# untitled.net
KiCad netlist of a schematic drawn in EAGLE
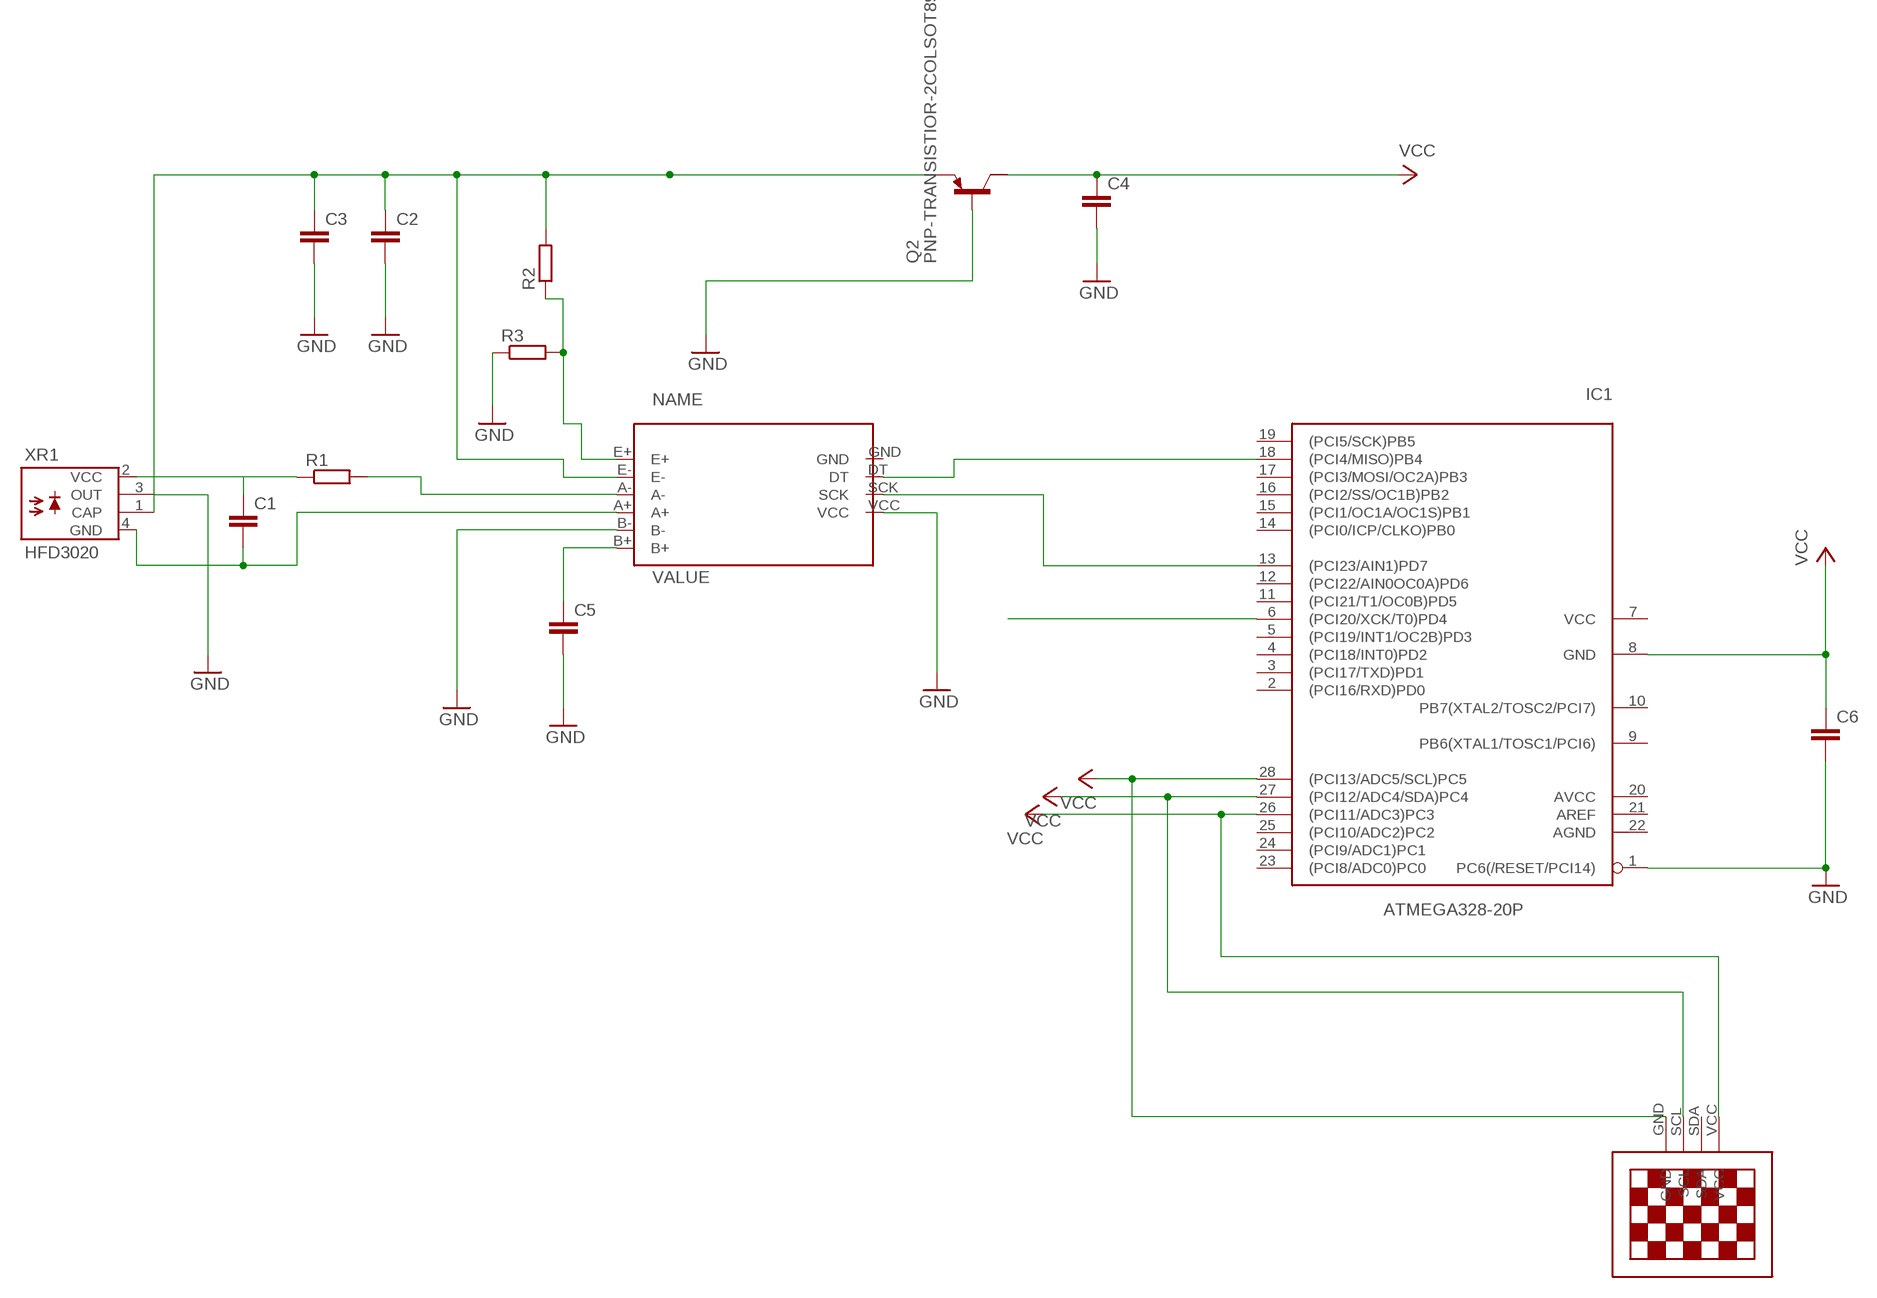
[diagram p0: schematic, sheet 1]

(export (version "E")
  (design (tool "Eeschema 10.0.6"))
  (components
    (comp (ref "C1")
      (value "C2,5-3")
      (footprint "eagle-import:C2.5-3")
      (libsource (lib "eagle-import") (part "C2,5-3"))
    )
    (comp (ref "C2")
      (value "C2,5-3")
      (footprint "eagle-import:C2.5-3")
      (libsource (lib "eagle-import") (part "C2,5-3"))
    )
    (comp (ref "C3")
      (value "C2,5-3")
      (footprint "eagle-import:C2.5-3")
      (libsource (lib "eagle-import") (part "C2,5-3"))
    )
    (comp (ref "C4")
      (value "C2,5-3")
      (footprint "eagle-import:C2.5-3")
      (libsource (lib "eagle-import") (part "C2,5-3"))
    )
    (comp (ref "C5")
      (value "C2,5-3")
      (footprint "eagle-import:C2.5-3")
      (libsource (lib "eagle-import") (part "C2,5-3"))
    )
    (comp (ref "C6")
      (value "C2,5-3")
      (footprint "eagle-import:C2.5-3")
      (libsource (lib "eagle-import") (part "C2,5-3"))
    )
    (comp (ref "IC1")
      (value "ATMEGA328-20P")
      (footprint "eagle-import:DIL28-3")
      (libsource (lib "eagle-import") (part "ATMEGA328P-20"))
    )
    (comp (ref "Q2")
      (value "PNP-TRANSISTIOR-2COLSOT89")
      (footprint "eagle-import:SOT89")
      (libsource (lib "eagle-import") (part "PNP-TRANSISTIOR-2COLSOT89"))
    )
    (comp (ref "R1")
      (value "R-EU_0204/2V")
      (footprint "eagle-import:0204V")
      (libsource (lib "eagle-import") (part "R-EU_0204/2V"))
    )
    (comp (ref "R2")
      (value "R-EU_0204/2V")
      (footprint "eagle-import:0204V")
      (libsource (lib "eagle-import") (part "R-EU_0204/2V"))
    )
    (comp (ref "R3")
      (value "R-EU_0204/2V")
      (footprint "eagle-import:0204V")
      (libsource (lib "eagle-import") (part "R-EU_0204/2V"))
    )
    (comp (ref "U$1")
      (value "13\"OLED13\"OLED")
      (footprint "eagle-import:1.3_OLED")
      (libsource (lib "eagle-import") (part "13{dblquote}OLED13{dblquote}OLED"))
    )
    (comp (ref "U$2")
      (value "HX711A")
      (footprint "eagle-import:HX711")
      (libsource (lib "eagle-import") (part "HX711A"))
    )
    (comp (ref "XR1")
      (value "HFD3020")
      (footprint "eagle-import:TO18PL4")
      (fields (field (name "MPN") "HFD3020-500-BBA"))
      (libsource (lib "eagle-import") (part "HFD3020"))
    )
  )
  (nets
    (net (code "1") (name "GND") (class "Default")
      (node (ref "C2") (pin "2") (pinfunction "2_2") (pintype "passive"))
      (node (ref "C3") (pin "2") (pinfunction "2_2") (pintype "passive"))
      (node (ref "C4") (pin "2") (pinfunction "2_2") (pintype "passive"))
      (node (ref "C5") (pin "2") (pinfunction "2_2") (pintype "passive"))
      (node (ref "C6") (pin "2") (pinfunction "2_2") (pintype "passive"))
      (node (ref "IC1") (pin "1") (pinfunction "PC6(/RESET/PCI14)_1") (pintype "bidirectional"))
      (node (ref "Q2") (pin "1") (pinfunction "B_1") (pintype "passive"))
      (node (ref "R3") (pin "1") (pinfunction "1_1") (pintype "passive"))
      (node (ref "U$2") (pin "B-") (pinfunction "B-_B-") (pintype "bidirectional"))
      (node (ref "U$2") (pin "VCC") (pinfunction "VCC_VCC") (pintype "bidirectional"))
      (node (ref "XR1") (pin "3") (pinfunction "OUT_3") (pintype "output"))
    )
    (net (code "2") (name "Net-(C5-Pad1)") (class "Default")
      (node (ref "C5") (pin "1") (pinfunction "1_1") (pintype "passive"))
      (node (ref "U$2") (pin "B+") (pinfunction "B+_B+") (pintype "bidirectional"))
    )
    (net (code "3") (name "Net-(IC1-(PCI4{slash}MISO)PB4)") (class "Default")
      (node (ref "IC1") (pin "18") (pinfunction "(PCI4/MISO)PB4_18") (pintype "bidirectional"))
      (node (ref "U$2") (pin "DT") (pinfunction "DT_DT") (pintype "bidirectional"))
    )
    (net (code "4") (name "Net-(IC1-(PCI23{slash}AIN1)PD7)") (class "Default")
      (node (ref "IC1") (pin "13") (pinfunction "(PCI23/AIN1)PD7_13") (pintype "bidirectional"))
      (node (ref "U$2") (pin "SCK") (pinfunction "SCK_SCK") (pintype "bidirectional"))
    )
    (net (code "5") (name "Net-(Q2-E)") (class "Default")
      (node (ref "C2") (pin "1") (pinfunction "1_1") (pintype "passive"))
      (node (ref "C3") (pin "1") (pinfunction "1_1") (pintype "passive"))
      (node (ref "Q2") (pin "3") (pinfunction "E_3") (pintype "passive"))
      (node (ref "R2") (pin "2") (pinfunction "2_2") (pintype "passive"))
      (node (ref "U$2") (pin "E-") (pinfunction "E-_E-") (pintype "bidirectional"))
      (node (ref "XR1") (pin "1") (pinfunction "CAP_1") (pintype "output"))
    )
    (net (code "6") (name "Net-(R1-Pad2)") (class "Default")
      (node (ref "R1") (pin "2") (pinfunction "2_2") (pintype "passive"))
      (node (ref "U$2") (pin "A-") (pinfunction "A-_A-") (pintype "bidirectional"))
    )
    (net (code "7") (name "Net-(R2-Pad1)") (class "Default")
      (node (ref "R2") (pin "1") (pinfunction "1_1") (pintype "passive"))
      (node (ref "R3") (pin "2") (pinfunction "2_2") (pintype "passive"))
      (node (ref "U$2") (pin "E+") (pinfunction "E+_E+") (pintype "bidirectional"))
    )
    (net (code "8") (name "Net-(XR1-GND)") (class "Default")
      (node (ref "C1") (pin "2") (pinfunction "2_2") (pintype "passive"))
      (node (ref "U$2") (pin "A+") (pinfunction "A+_A+") (pintype "bidirectional"))
      (node (ref "XR1") (pin "4") (pinfunction "GND_4") (pintype "power_in"))
    )
    (net (code "9") (name "Net-(XR1-VCC)") (class "Default")
      (node (ref "R1") (pin "1") (pinfunction "1_1") (pintype "passive"))
      (node (ref "XR1") (pin "2") (pinfunction "VCC_2") (pintype "power_in"))
    )
    (net (code "10") (name "VCC") (class "Default")
      (node (ref "C4") (pin "1") (pinfunction "1_1") (pintype "passive"))
      (node (ref "C6") (pin "1") (pinfunction "1_1") (pintype "passive"))
      (node (ref "IC1") (pin "26") (pinfunction "(PCI11/ADC3)PC3_26") (pintype "bidirectional"))
      (node (ref "IC1") (pin "27") (pinfunction "(PCI12/ADC4/SDA)PC4_27") (pintype "bidirectional"))
      (node (ref "IC1") (pin "28") (pinfunction "(PCI13/ADC5/SCL)PC5_28") (pintype "bidirectional"))
      (node (ref "IC1") (pin "8") (pinfunction "GND_8") (pintype "bidirectional"))
      (node (ref "Q2") (pin "2") (pinfunction "C_2") (pintype "passive"))
      (node (ref "U$1") (pin "GND") (pinfunction "GND_GND") (pintype "bidirectional"))
      (node (ref "U$1") (pin "SCL") (pinfunction "SCL_SCL") (pintype "bidirectional"))
      (node (ref "U$1") (pin "VCC") (pinfunction "VCC_VCC") (pintype "bidirectional"))
    )
    (net (code "11") (name "unconnected-(C1-Pad1)") (class "Default")
      (node (ref "C1") (pin "1") (pinfunction "1_1") (pintype "passive"))
    )
    (net (code "12") (name "unconnected-(IC1-(PCI0{slash}ICP{slash}CLKO)PB0-Pad14)") (class "Default")
      (node (ref "IC1") (pin "14") (pinfunction "(PCI0/ICP/CLKO)PB0_14") (pintype "bidirectional"))
    )
    (net (code "13") (name "unconnected-(IC1-(PCI1{slash}OC1A{slash}OC1S)PB1-Pad15)") (class "Default")
      (node (ref "IC1") (pin "15") (pinfunction "(PCI1/OC1A/OC1S)PB1_15") (pintype "bidirectional"))
    )
    (net (code "14") (name "unconnected-(IC1-(PCI2{slash}SS{slash}OC1B)PB2-Pad16)") (class "Default")
      (node (ref "IC1") (pin "16") (pinfunction "(PCI2/SS/OC1B)PB2_16") (pintype "bidirectional"))
    )
    (net (code "15") (name "unconnected-(IC1-(PCI3{slash}MOSI{slash}OC2A)PB3-Pad17)") (class "Default")
      (node (ref "IC1") (pin "17") (pinfunction "(PCI3/MOSI/OC2A)PB3_17") (pintype "bidirectional"))
    )
    (net (code "16") (name "unconnected-(IC1-(PCI5{slash}SCK)PB5-Pad19)") (class "Default")
      (node (ref "IC1") (pin "19") (pinfunction "(PCI5/SCK)PB5_19") (pintype "bidirectional"))
    )
    (net (code "17") (name "unconnected-(IC1-(PCI8{slash}ADC0)PC0-Pad23)") (class "Default")
      (node (ref "IC1") (pin "23") (pinfunction "(PCI8/ADC0)PC0_23") (pintype "bidirectional"))
    )
    (net (code "18") (name "unconnected-(IC1-(PCI9{slash}ADC1)PC1-Pad24)") (class "Default")
      (node (ref "IC1") (pin "24") (pinfunction "(PCI9/ADC1)PC1_24") (pintype "bidirectional"))
    )
    (net (code "19") (name "unconnected-(IC1-(PCI10{slash}ADC2)PC2-Pad25)") (class "Default")
      (node (ref "IC1") (pin "25") (pinfunction "(PCI10/ADC2)PC2_25") (pintype "bidirectional"))
    )
    (net (code "20") (name "unconnected-(IC1-(PCI16{slash}RXD)PD0-Pad2)") (class "Default")
      (node (ref "IC1") (pin "2") (pinfunction "(PCI16/RXD)PD0_2") (pintype "bidirectional"))
    )
    (net (code "21") (name "unconnected-(IC1-(PCI17{slash}TXD)PD1-Pad3)") (class "Default")
      (node (ref "IC1") (pin "3") (pinfunction "(PCI17/TXD)PD1_3") (pintype "bidirectional"))
    )
    (net (code "22") (name "unconnected-(IC1-(PCI18{slash}INT0)PD2-Pad4)") (class "Default")
      (node (ref "IC1") (pin "4") (pinfunction "(PCI18/INT0)PD2_4") (pintype "bidirectional"))
    )
    (net (code "23") (name "unconnected-(IC1-(PCI19{slash}INT1{slash}OC2B)PD3-Pad5)") (class "Default")
      (node (ref "IC1") (pin "5") (pinfunction "(PCI19/INT1/OC2B)PD3_5") (pintype "bidirectional"))
    )
    (net (code "24") (name "unconnected-(IC1-(PCI20{slash}XCK{slash}T0)PD4-Pad6)") (class "Default")
      (node (ref "IC1") (pin "6") (pinfunction "(PCI20/XCK/T0)PD4_6") (pintype "bidirectional"))
    )
    (net (code "25") (name "unconnected-(IC1-(PCI21{slash}T1{slash}OC0B)PD5-Pad11)") (class "Default")
      (node (ref "IC1") (pin "11") (pinfunction "(PCI21/T1/OC0B)PD5_11") (pintype "bidirectional"))
    )
    (net (code "26") (name "unconnected-(IC1-(PCI22{slash}AIN0OC0A)PD6-Pad12)") (class "Default")
      (node (ref "IC1") (pin "12") (pinfunction "(PCI22/AIN0OC0A)PD6_12") (pintype "bidirectional"))
    )
    (net (code "27") (name "unconnected-(IC1-AGND-Pad22)") (class "Default")
      (node (ref "IC1") (pin "22") (pinfunction "AGND_22") (pintype "bidirectional"))
    )
    (net (code "28") (name "unconnected-(IC1-AREF-Pad21)") (class "Default")
      (node (ref "IC1") (pin "21") (pinfunction "AREF_21") (pintype "bidirectional"))
    )
    (net (code "29") (name "unconnected-(IC1-AVCC-Pad20)") (class "Default")
      (node (ref "IC1") (pin "20") (pinfunction "AVCC_20") (pintype "bidirectional"))
    )
    (net (code "30") (name "unconnected-(IC1-PB6(XTAL1{slash}TOSC1{slash}PCI6)-Pad9)") (class "Default")
      (node (ref "IC1") (pin "9") (pinfunction "PB6(XTAL1/TOSC1/PCI6)_9") (pintype "bidirectional"))
    )
    (net (code "31") (name "unconnected-(IC1-PB7(XTAL2{slash}TOSC2{slash}PCI7)-Pad10)") (class "Default")
      (node (ref "IC1") (pin "10") (pinfunction "PB7(XTAL2/TOSC2/PCI7)_10") (pintype "bidirectional"))
    )
    (net (code "32") (name "unconnected-(IC1-VCC-Pad7)") (class "Default")
      (node (ref "IC1") (pin "7") (pinfunction "VCC_7") (pintype "bidirectional"))
    )
    (net (code "33") (name "unconnected-(Q2-C{slash}-Pad2@1)") (class "Default")
      (node (ref "Q2") (pin "2@1") (pinfunction "C/_2@1") (pintype "passive"))
    )
    (net (code "34") (name "unconnected-(U$1-PadSDA)") (class "Default")
      (node (ref "U$1") (pin "SDA") (pinfunction "SDA_SDA") (pintype "bidirectional"))
    )
    (net (code "35") (name "unconnected-(U$2-PadGND)") (class "Default")
      (node (ref "U$2") (pin "GND") (pinfunction "GND_GND") (pintype "bidirectional"))
    )
  )
)
